# 6_eMMC.net
KiCad netlist of a schematic drawn in Altium Designer
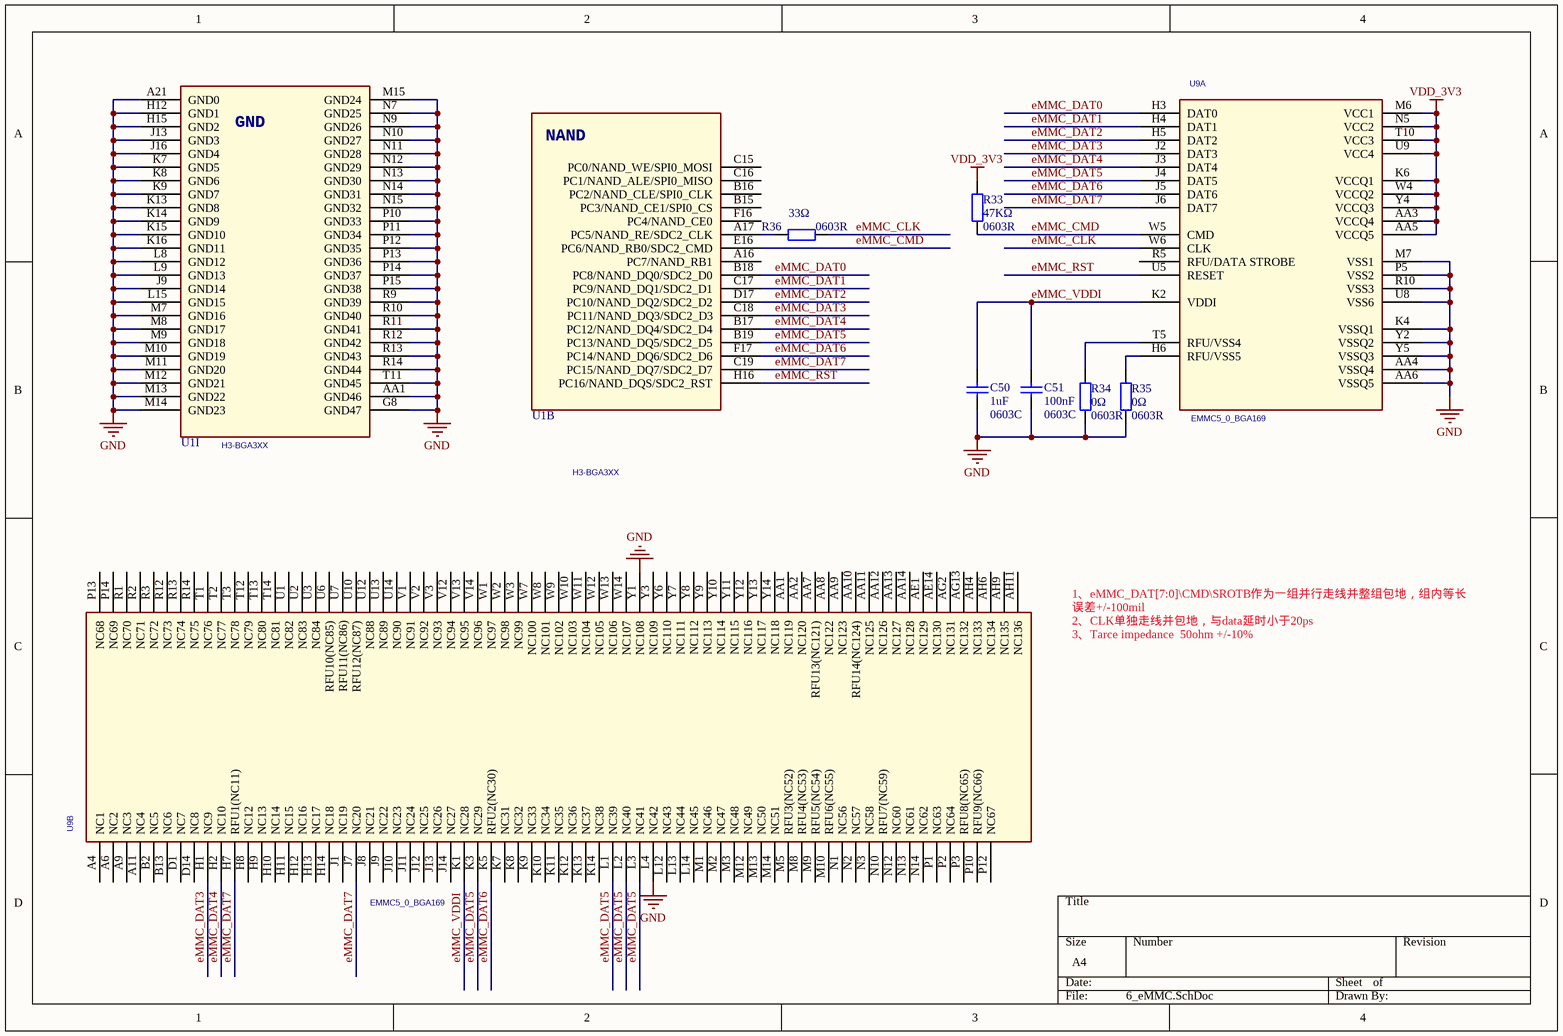
[diagram p0: 6_eMMC.SchDoc]

(export (version "E")
  (design (tool "Eeschema 10.0.6"))
  (components
    (comp (ref "C50")
      (value "1uF")
      (footprint "0603_C")
      (description "贴片电容")
      (fields (field (name "PACKAGE") "0603C"))
      (libsource (lib "Miscellaneous Devices LC") (part "0402 1nF (102) 10% 50V"))
    )
    (comp (ref "C51")
      (value "100nF")
      (footprint "0603_C")
      (description "贴片电容")
      (fields (field (name "PACKAGE") "0603C"))
      (libsource (lib "Miscellaneous Devices LC") (part "0402 1nF (102) 10% 50V"))
    )
    (comp (ref "R33")
      (value "47KΩ")
      (footprint "0603_R")
      (description "贴片电阻")
      (fields (field (name "PACKAGE") "0603R"))
      (libsource (lib "") (part "0402 1KΩ (1001) 1%_1"))
    )
    (comp (ref "R34")
      (value "0Ω")
      (footprint "0603_R")
      (description "贴片电阻")
      (fields (field (name "PACKAGE") "0603R"))
      (libsource (lib "") (part "0402 1KΩ (1001) 1%_1"))
    )
    (comp (ref "R35")
      (value "0Ω")
      (footprint "0603_R")
      (description "贴片电阻")
      (fields (field (name "PACKAGE") "0603R"))
      (libsource (lib "") (part "0402 1KΩ (1001) 1%_1"))
    )
    (comp (ref "R36")
      (value "33Ω")
      (footprint "0603_R")
      (description "贴片电阻")
      (fields (field (name "PACKAGE") "0603R"))
      (libsource (lib "Miscellaneous Devices LC") (part "0402 1KΩ (1001) 1%"))
    )
    (comp (ref "U1")
      (value "H3-BGA3XX")
      (footprint "BGA347P0_65B14X14")
      (libsource (lib "MAGNET_L") (part "H3-BGA3XX"))
    )
    (comp (ref "U9")
      (value "EMMC5_0_BGA169")
      (footprint "BGA169P0_50B12_00X16_00H1_00")
      (libsource (lib "H3_PROTOTYPE_DDR3_16X2_V3_0_20141113") (part "EMMC5_0_BGA169"))
    )
  )
  (nets
    (net (code "1") (name "/eMMC_CLK") (class "Default")
      (node (ref "R36") (pin "2") (pinfunction "2_2") (pintype "passive"))
      (node (ref "U9") (pin "W6") (pinfunction "CLK_W6") (pintype "passive"))
    )
    (net (code "2") (name "/eMMC_CMD") (class "Default")
      (node (ref "R33") (pin "2") (pinfunction "2_2") (pintype "passive"))
      (node (ref "U1") (pin "E16") (pinfunction "PC6/NAND_RB0/SDC2_CMD_E16") (pintype "passive"))
      (node (ref "U9") (pin "W5") (pinfunction "CMD_W5") (pintype "passive"))
    )
    (net (code "3") (name "/eMMC_DAT0") (class "Default")
      (node (ref "U1") (pin "B18") (pinfunction "PC8/NAND_DQ0/SDC2_D0_B18") (pintype "passive"))
      (node (ref "U9") (pin "H3") (pinfunction "DAT0_H3") (pintype "passive"))
    )
    (net (code "4") (name "/eMMC_DAT1") (class "Default")
      (node (ref "U1") (pin "C17") (pinfunction "PC9/NAND_DQ1/SDC2_D1_C17") (pintype "passive"))
      (node (ref "U9") (pin "H4") (pinfunction "DAT1_H4") (pintype "passive"))
    )
    (net (code "5") (name "/eMMC_DAT2") (class "Default")
      (node (ref "U1") (pin "D17") (pinfunction "PC10/NAND_DQ2/SDC2_D2_D17") (pintype "passive"))
      (node (ref "U9") (pin "H5") (pinfunction "DAT2_H5") (pintype "passive"))
    )
    (net (code "6") (name "/eMMC_DAT3") (class "Default")
      (node (ref "U1") (pin "C18") (pinfunction "PC11/NAND_DQ3/SDC2_D3_C18") (pintype "passive"))
      (node (ref "U9") (pin "H1") (pinfunction "NC9_H1") (pintype "passive"))
      (node (ref "U9") (pin "J2") (pinfunction "DAT3_J2") (pintype "passive"))
    )
    (net (code "7") (name "/eMMC_DAT4") (class "Default")
      (node (ref "U1") (pin "B17") (pinfunction "PC12/NAND_DQ4/SDC2_D4_B17") (pintype "passive"))
      (node (ref "U9") (pin "H2") (pinfunction "NC10_H2") (pintype "passive"))
      (node (ref "U9") (pin "J3") (pinfunction "DAT4_J3") (pintype "passive"))
    )
    (net (code "8") (name "/eMMC_DAT5") (class "Default")
      (node (ref "U1") (pin "B19") (pinfunction "PC13/NAND_DQ5/SDC2_D5_B19") (pintype "passive"))
      (node (ref "U9") (pin "J4") (pinfunction "DAT5_J4") (pintype "passive"))
      (node (ref "U9") (pin "K3") (pinfunction "NC29_K3") (pintype "passive"))
      (node (ref "U9") (pin "L1") (pinfunction "NC39_L1") (pintype "passive"))
      (node (ref "U9") (pin "L2") (pinfunction "NC40_L2") (pintype "passive"))
      (node (ref "U9") (pin "L3") (pinfunction "NC41_L3") (pintype "passive"))
    )
    (net (code "9") (name "/eMMC_DAT6") (class "Default")
      (node (ref "U1") (pin "F17") (pinfunction "PC14/NAND_DQ6/SDC2_D6_F17") (pintype "passive"))
      (node (ref "U9") (pin "J5") (pinfunction "DAT6_J5") (pintype "passive"))
      (node (ref "U9") (pin "K5") (pinfunction "RFU2(NC30)_K5") (pintype "passive"))
    )
    (net (code "10") (name "/eMMC_DAT7") (class "Default")
      (node (ref "U1") (pin "C19") (pinfunction "PC15/NAND_DQ7/SDC2_D7_C19") (pintype "passive"))
      (node (ref "U9") (pin "H7") (pinfunction "RFU1(NC11)_H7") (pintype "passive"))
      (node (ref "U9") (pin "J6") (pinfunction "DAT7_J6") (pintype "passive"))
      (node (ref "U9") (pin "J7") (pinfunction "NC20_J7") (pintype "passive"))
    )
    (net (code "11") (name "/eMMC_RST") (class "Default")
      (node (ref "U1") (pin "H16") (pinfunction "PC16/NAND_DQS/SDC2_RST_H16") (pintype "passive"))
      (node (ref "U9") (pin "U5") (pinfunction "RESET_U5") (pintype "passive"))
    )
    (net (code "12") (name "/eMMC_VDDI") (class "Default")
      (node (ref "C50") (pin "1") (pinfunction "1_1") (pintype "passive"))
      (node (ref "C51") (pin "1") (pinfunction "1_1") (pintype "passive"))
      (node (ref "U9") (pin "K1") (pinfunction "NC28_K1") (pintype "passive"))
      (node (ref "U9") (pin "K2") (pinfunction "VDDI_K2") (pintype "passive"))
    )
    (net (code "13") (name "GND") (class "Default")
      (node (ref "C50") (pin "2") (pinfunction "2_2") (pintype "passive"))
      (node (ref "C51") (pin "2") (pinfunction "2_2") (pintype "passive"))
      (node (ref "R34") (pin "2") (pinfunction "2_2") (pintype "passive"))
      (node (ref "R35") (pin "2") (pinfunction "2_2") (pintype "passive"))
      (node (ref "U1") (pin "A21") (pinfunction "GND0_A21") (pintype "passive"))
      (node (ref "U1") (pin "AA1") (pinfunction "GND46_AA1") (pintype "passive"))
      (node (ref "U1") (pin "G8") (pinfunction "GND47_G8") (pintype "passive"))
      (node (ref "U1") (pin "H12") (pinfunction "GND1_H12") (pintype "passive"))
      (node (ref "U1") (pin "H15") (pinfunction "GND2_H15") (pintype "passive"))
      (node (ref "U1") (pin "J13") (pinfunction "GND3_J13") (pintype "passive"))
      (node (ref "U1") (pin "J16") (pinfunction "GND4_J16") (pintype "passive"))
      (node (ref "U1") (pin "J9") (pinfunction "GND14_J9") (pintype "passive"))
      (node (ref "U1") (pin "K13") (pinfunction "GND8_K13") (pintype "passive"))
      (node (ref "U1") (pin "K14") (pinfunction "GND9_K14") (pintype "passive"))
      (node (ref "U1") (pin "K15") (pinfunction "GND10_K15") (pintype "passive"))
      (node (ref "U1") (pin "K16") (pinfunction "GND11_K16") (pintype "passive"))
      (node (ref "U1") (pin "K7") (pinfunction "GND5_K7") (pintype "passive"))
      (node (ref "U1") (pin "K8") (pinfunction "GND6_K8") (pintype "passive"))
      (node (ref "U1") (pin "K9") (pinfunction "GND7_K9") (pintype "passive"))
      (node (ref "U1") (pin "L15") (pinfunction "GND15_L15") (pintype "passive"))
      (node (ref "U1") (pin "L8") (pinfunction "GND12_L8") (pintype "passive"))
      (node (ref "U1") (pin "L9") (pinfunction "GND13_L9") (pintype "passive"))
      (node (ref "U1") (pin "M10") (pinfunction "GND19_M10") (pintype "passive"))
      (node (ref "U1") (pin "M11") (pinfunction "GND20_M11") (pintype "passive"))
      (node (ref "U1") (pin "M12") (pinfunction "GND21_M12") (pintype "passive"))
      (node (ref "U1") (pin "M13") (pinfunction "GND22_M13") (pintype "passive"))
      (node (ref "U1") (pin "M14") (pinfunction "GND23_M14") (pintype "passive"))
      (node (ref "U1") (pin "M15") (pinfunction "GND24_M15") (pintype "passive"))
      (node (ref "U1") (pin "M7") (pinfunction "GND16_M7") (pintype "passive"))
      (node (ref "U1") (pin "M8") (pinfunction "GND17_M8") (pintype "passive"))
      (node (ref "U1") (pin "M9") (pinfunction "GND18_M9") (pintype "passive"))
      (node (ref "U1") (pin "N10") (pinfunction "GND27_N10") (pintype "passive"))
      (node (ref "U1") (pin "N11") (pinfunction "GND28_N11") (pintype "passive"))
      (node (ref "U1") (pin "N12") (pinfunction "GND29_N12") (pintype "passive"))
      (node (ref "U1") (pin "N13") (pinfunction "GND30_N13") (pintype "passive"))
      (node (ref "U1") (pin "N14") (pinfunction "GND31_N14") (pintype "passive"))
      (node (ref "U1") (pin "N15") (pinfunction "GND32_N15") (pintype "passive"))
      (node (ref "U1") (pin "N7") (pinfunction "GND25_N7") (pintype "passive"))
      (node (ref "U1") (pin "N9") (pinfunction "GND26_N9") (pintype "passive"))
      (node (ref "U1") (pin "P10") (pinfunction "GND33_P10") (pintype "passive"))
      (node (ref "U1") (pin "P11") (pinfunction "GND34_P11") (pintype "passive"))
      (node (ref "U1") (pin "P12") (pinfunction "GND35_P12") (pintype "passive"))
      (node (ref "U1") (pin "P13") (pinfunction "GND36_P13") (pintype "passive"))
      (node (ref "U1") (pin "P14") (pinfunction "GND37_P14") (pintype "passive"))
      (node (ref "U1") (pin "P15") (pinfunction "GND38_P15") (pintype "passive"))
      (node (ref "U1") (pin "R10") (pinfunction "GND40_R10") (pintype "passive"))
      (node (ref "U1") (pin "R11") (pinfunction "GND41_R11") (pintype "passive"))
      (node (ref "U1") (pin "R12") (pinfunction "GND42_R12") (pintype "passive"))
      (node (ref "U1") (pin "R13") (pinfunction "GND43_R13") (pintype "passive"))
      (node (ref "U1") (pin "R14") (pinfunction "GND44_R14") (pintype "passive"))
      (node (ref "U1") (pin "R9") (pinfunction "GND39_R9") (pintype "passive"))
      (node (ref "U1") (pin "T11") (pinfunction "GND45_T11") (pintype "passive"))
      (node (ref "U9") (pin "AA4") (pinfunction "VSSQ4_AA4") (pintype "passive"))
      (node (ref "U9") (pin "AA6") (pinfunction "VSSQ5_AA6") (pintype "passive"))
      (node (ref "U9") (pin "K4") (pinfunction "VSSQ1_K4") (pintype "passive"))
      (node (ref "U9") (pin "L4") (pinfunction "NC42_L4") (pintype "passive"))
      (node (ref "U9") (pin "M7") (pinfunction "VSS1_M7") (pintype "passive"))
      (node (ref "U9") (pin "P5") (pinfunction "VSS2_P5") (pintype "passive"))
      (node (ref "U9") (pin "R10") (pinfunction "VSS3_R10") (pintype "passive"))
      (node (ref "U9") (pin "U8") (pinfunction "VSS6_U8") (pintype "passive"))
      (node (ref "U9") (pin "Y1") (pinfunction "NC108_Y1") (pintype "passive"))
      (node (ref "U9") (pin "Y2") (pinfunction "VSSQ2_Y2") (pintype "passive"))
      (node (ref "U9") (pin "Y5") (pinfunction "VSSQ3_Y5") (pintype "passive"))
    )
    (net (code "14") (name "Net-(U1B-PC5{slash}NAND_RE{slash}SDC2_CLK)") (class "Default")
      (node (ref "R36") (pin "1") (pinfunction "1_1") (pintype "passive"))
      (node (ref "U1") (pin "A17") (pinfunction "PC5/NAND_RE/SDC2_CLK_A17") (pintype "passive"))
    )
    (net (code "15") (name "Net-(U9A-RFU{slash}VSS4)") (class "Default")
      (node (ref "R34") (pin "1") (pinfunction "1_1") (pintype "passive"))
      (node (ref "U9") (pin "T5") (pinfunction "RFU/VSS4_T5") (pintype "passive"))
    )
    (net (code "16") (name "Net-(U9A-RFU{slash}VSS5)") (class "Default")
      (node (ref "R35") (pin "1") (pinfunction "1_1") (pintype "passive"))
      (node (ref "U9") (pin "H6") (pinfunction "RFU/VSS5_H6") (pintype "passive"))
    )
    (net (code "17") (name "VDD_3V3") (class "Default")
      (node (ref "R33") (pin "1") (pinfunction "1_1") (pintype "passive"))
      (node (ref "U9") (pin "AA3") (pinfunction "VCCQ4_AA3") (pintype "passive"))
      (node (ref "U9") (pin "AA5") (pinfunction "VCCQ5_AA5") (pintype "passive"))
      (node (ref "U9") (pin "K6") (pinfunction "VCCQ1_K6") (pintype "passive"))
      (node (ref "U9") (pin "M6") (pinfunction "VCC1_M6") (pintype "passive"))
      (node (ref "U9") (pin "N5") (pinfunction "VCC2_N5") (pintype "passive"))
      (node (ref "U9") (pin "T10") (pinfunction "VCC3_T10") (pintype "passive"))
      (node (ref "U9") (pin "U9") (pinfunction "VCC4_U9") (pintype "passive"))
      (node (ref "U9") (pin "W4") (pinfunction "VCCQ2_W4") (pintype "passive"))
      (node (ref "U9") (pin "Y4") (pinfunction "VCCQ3_Y4") (pintype "passive"))
    )
    (net (code "18") (name "unconnected-(U1B-PC0{slash}NAND_WE{slash}SPI0_MOSI-PadC15)") (class "Default")
      (node (ref "U1") (pin "C15") (pinfunction "PC0/NAND_WE/SPI0_MOSI_C15") (pintype "passive"))
    )
    (net (code "19") (name "unconnected-(U1B-PC1{slash}NAND_ALE{slash}SPI0_MISO-PadC16)") (class "Default")
      (node (ref "U1") (pin "C16") (pinfunction "PC1/NAND_ALE/SPI0_MISO_C16") (pintype "passive"))
    )
    (net (code "20") (name "unconnected-(U1B-PC2{slash}NAND_CLE{slash}SPI0_CLK-PadB16)") (class "Default")
      (node (ref "U1") (pin "B16") (pinfunction "PC2/NAND_CLE/SPI0_CLK_B16") (pintype "passive"))
    )
    (net (code "21") (name "unconnected-(U1B-PC3{slash}NAND_CE1{slash}SPI0_CS-PadB15)") (class "Default")
      (node (ref "U1") (pin "B15") (pinfunction "PC3/NAND_CE1/SPI0_CS_B15") (pintype "passive"))
    )
    (net (code "22") (name "unconnected-(U1B-PC4{slash}NAND_CE0-PadF16)") (class "Default")
      (node (ref "U1") (pin "F16") (pinfunction "PC4/NAND_CE0_F16") (pintype "passive"))
    )
    (net (code "23") (name "unconnected-(U1B-PC7{slash}NAND_RB1-PadA16)") (class "Default")
      (node (ref "U1") (pin "A16") (pinfunction "PC7/NAND_RB1_A16") (pintype "passive"))
    )
    (net (code "24") (name "unconnected-(U9A-RFU{slash}DATA_STROBE-PadR5)") (class "Default")
      (node (ref "U9") (pin "R5") (pinfunction "RFU/DATA_STROBE_R5") (pintype "passive"))
    )
    (net (code "25") (name "unconnected-(U9B-NC1-PadA4)") (class "Default")
      (node (ref "U9") (pin "A4") (pinfunction "NC1_A4") (pintype "passive"))
    )
    (net (code "26") (name "unconnected-(U9B-NC2-PadA6)") (class "Default")
      (node (ref "U9") (pin "A6") (pinfunction "NC2_A6") (pintype "passive"))
    )
    (net (code "27") (name "unconnected-(U9B-NC3-PadA9)") (class "Default")
      (node (ref "U9") (pin "A9") (pinfunction "NC3_A9") (pintype "passive"))
    )
    (net (code "28") (name "unconnected-(U9B-NC4-PadA11)") (class "Default")
      (node (ref "U9") (pin "A11") (pinfunction "NC4_A11") (pintype "passive"))
    )
    (net (code "29") (name "unconnected-(U9B-NC5-PadB2)") (class "Default")
      (node (ref "U9") (pin "B2") (pinfunction "NC5_B2") (pintype "passive"))
    )
    (net (code "30") (name "unconnected-(U9B-NC6-PadB13)") (class "Default")
      (node (ref "U9") (pin "B13") (pinfunction "NC6_B13") (pintype "passive"))
    )
    (net (code "31") (name "unconnected-(U9B-NC7-PadD1)") (class "Default")
      (node (ref "U9") (pin "D1") (pinfunction "NC7_D1") (pintype "passive"))
    )
    (net (code "32") (name "unconnected-(U9B-NC8-PadD14)") (class "Default")
      (node (ref "U9") (pin "D14") (pinfunction "NC8_D14") (pintype "passive"))
    )
    (net (code "33") (name "unconnected-(U9B-NC12-PadH8)") (class "Default")
      (node (ref "U9") (pin "H8") (pinfunction "NC12_H8") (pintype "passive"))
    )
    (net (code "34") (name "unconnected-(U9B-NC13-PadH9)") (class "Default")
      (node (ref "U9") (pin "H9") (pinfunction "NC13_H9") (pintype "passive"))
    )
    (net (code "35") (name "unconnected-(U9B-NC14-PadH10)") (class "Default")
      (node (ref "U9") (pin "H10") (pinfunction "NC14_H10") (pintype "passive"))
    )
    (net (code "36") (name "unconnected-(U9B-NC15-PadH11)") (class "Default")
      (node (ref "U9") (pin "H11") (pinfunction "NC15_H11") (pintype "passive"))
    )
    (net (code "37") (name "unconnected-(U9B-NC16-PadH12)") (class "Default")
      (node (ref "U9") (pin "H12") (pinfunction "NC16_H12") (pintype "passive"))
    )
    (net (code "38") (name "unconnected-(U9B-NC17-PadH13)") (class "Default")
      (node (ref "U9") (pin "H13") (pinfunction "NC17_H13") (pintype "passive"))
    )
    (net (code "39") (name "unconnected-(U9B-NC18-PadH14)") (class "Default")
      (node (ref "U9") (pin "H14") (pinfunction "NC18_H14") (pintype "passive"))
    )
    (net (code "40") (name "unconnected-(U9B-NC19-PadJ1)") (class "Default")
      (node (ref "U9") (pin "J1") (pinfunction "NC19_J1") (pintype "passive"))
    )
    (net (code "41") (name "unconnected-(U9B-NC21-PadJ8)") (class "Default")
      (node (ref "U9") (pin "J8") (pinfunction "NC21_J8") (pintype "passive"))
    )
    (net (code "42") (name "unconnected-(U9B-NC22-PadJ9)") (class "Default")
      (node (ref "U9") (pin "J9") (pinfunction "NC22_J9") (pintype "passive"))
    )
    (net (code "43") (name "unconnected-(U9B-NC23-PadJ10)") (class "Default")
      (node (ref "U9") (pin "J10") (pinfunction "NC23_J10") (pintype "passive"))
    )
    (net (code "44") (name "unconnected-(U9B-NC24-PadJ11)") (class "Default")
      (node (ref "U9") (pin "J11") (pinfunction "NC24_J11") (pintype "passive"))
    )
    (net (code "45") (name "unconnected-(U9B-NC25-PadJ12)") (class "Default")
      (node (ref "U9") (pin "J12") (pinfunction "NC25_J12") (pintype "passive"))
    )
    (net (code "46") (name "unconnected-(U9B-NC26-PadJ13)") (class "Default")
      (node (ref "U9") (pin "J13") (pinfunction "NC26_J13") (pintype "passive"))
    )
    (net (code "47") (name "unconnected-(U9B-NC27-PadJ14)") (class "Default")
      (node (ref "U9") (pin "J14") (pinfunction "NC27_J14") (pintype "passive"))
    )
    (net (code "48") (name "unconnected-(U9B-NC31-PadK7)") (class "Default")
      (node (ref "U9") (pin "K7") (pinfunction "NC31_K7") (pintype "passive"))
    )
    (net (code "49") (name "unconnected-(U9B-NC32-PadK8)") (class "Default")
      (node (ref "U9") (pin "K8") (pinfunction "NC32_K8") (pintype "passive"))
    )
    (net (code "50") (name "unconnected-(U9B-NC33-PadK9)") (class "Default")
      (node (ref "U9") (pin "K9") (pinfunction "NC33_K9") (pintype "passive"))
    )
    (net (code "51") (name "unconnected-(U9B-NC34-PadK10)") (class "Default")
      (node (ref "U9") (pin "K10") (pinfunction "NC34_K10") (pintype "passive"))
    )
    (net (code "52") (name "unconnected-(U9B-NC35-PadK11)") (class "Default")
      (node (ref "U9") (pin "K11") (pinfunction "NC35_K11") (pintype "passive"))
    )
    (net (code "53") (name "unconnected-(U9B-NC36-PadK12)") (class "Default")
      (node (ref "U9") (pin "K12") (pinfunction "NC36_K12") (pintype "passive"))
    )
    (net (code "54") (name "unconnected-(U9B-NC37-PadK13)") (class "Default")
      (node (ref "U9") (pin "K13") (pinfunction "NC37_K13") (pintype "passive"))
    )
    (net (code "55") (name "unconnected-(U9B-NC38-PadK14)") (class "Default")
      (node (ref "U9") (pin "K14") (pinfunction "NC38_K14") (pintype "passive"))
    )
    (net (code "56") (name "unconnected-(U9B-NC43-PadL12)") (class "Default")
      (node (ref "U9") (pin "L12") (pinfunction "NC43_L12") (pintype "passive"))
    )
    (net (code "57") (name "unconnected-(U9B-NC44-PadL13)") (class "Default")
      (node (ref "U9") (pin "L13") (pinfunction "NC44_L13") (pintype "passive"))
    )
    (net (code "58") (name "unconnected-(U9B-NC45-PadL14)") (class "Default")
      (node (ref "U9") (pin "L14") (pinfunction "NC45_L14") (pintype "passive"))
    )
    (net (code "59") (name "unconnected-(U9B-NC46-PadM1)") (class "Default")
      (node (ref "U9") (pin "M1") (pinfunction "NC46_M1") (pintype "passive"))
    )
    (net (code "60") (name "unconnected-(U9B-NC47-PadM2)") (class "Default")
      (node (ref "U9") (pin "M2") (pinfunction "NC47_M2") (pintype "passive"))
    )
    (net (code "61") (name "unconnected-(U9B-NC48-PadM3)") (class "Default")
      (node (ref "U9") (pin "M3") (pinfunction "NC48_M3") (pintype "passive"))
    )
    (net (code "62") (name "unconnected-(U9B-NC49-PadM12)") (class "Default")
      (node (ref "U9") (pin "M12") (pinfunction "NC49_M12") (pintype "passive"))
    )
    (net (code "63") (name "unconnected-(U9B-NC50-PadM13)") (class "Default")
      (node (ref "U9") (pin "M13") (pinfunction "NC50_M13") (pintype "passive"))
    )
    (net (code "64") (name "unconnected-(U9B-NC51-PadM14)") (class "Default")
      (node (ref "U9") (pin "M14") (pinfunction "NC51_M14") (pintype "passive"))
    )
    (net (code "65") (name "unconnected-(U9B-NC56-PadN1)") (class "Default")
      (node (ref "U9") (pin "N1") (pinfunction "NC56_N1") (pintype "passive"))
    )
    (net (code "66") (name "unconnected-(U9B-NC57-PadN2)") (class "Default")
      (node (ref "U9") (pin "N2") (pinfunction "NC57_N2") (pintype "passive"))
    )
    (net (code "67") (name "unconnected-(U9B-NC58-PadN3)") (class "Default")
      (node (ref "U9") (pin "N3") (pinfunction "NC58_N3") (pintype "passive"))
    )
    (net (code "68") (name "unconnected-(U9B-NC60-PadN12)") (class "Default")
      (node (ref "U9") (pin "N12") (pinfunction "NC60_N12") (pintype "passive"))
    )
    (net (code "69") (name "unconnected-(U9B-NC61-PadN13)") (class "Default")
      (node (ref "U9") (pin "N13") (pinfunction "NC61_N13") (pintype "passive"))
    )
    (net (code "70") (name "unconnected-(U9B-NC62-PadN14)") (class "Default")
      (node (ref "U9") (pin "N14") (pinfunction "NC62_N14") (pintype "passive"))
    )
    (net (code "71") (name "unconnected-(U9B-NC63-PadP1)") (class "Default")
      (node (ref "U9") (pin "P1") (pinfunction "NC63_P1") (pintype "passive"))
    )
    (net (code "72") (name "unconnected-(U9B-NC64-PadP2)") (class "Default")
      (node (ref "U9") (pin "P2") (pinfunction "NC64_P2") (pintype "passive"))
    )
    (net (code "73") (name "unconnected-(U9B-NC67-PadP12)") (class "Default")
      (node (ref "U9") (pin "P12") (pinfunction "NC67_P12") (pintype "passive"))
    )
    (net (code "74") (name "unconnected-(U9B-NC68-PadP13)") (class "Default")
      (node (ref "U9") (pin "P13") (pinfunction "NC68_P13") (pintype "passive"))
    )
    (net (code "75") (name "unconnected-(U9B-NC69-PadP14)") (class "Default")
      (node (ref "U9") (pin "P14") (pinfunction "NC69_P14") (pintype "passive"))
    )
    (net (code "76") (name "unconnected-(U9B-NC70-PadR1)") (class "Default")
      (node (ref "U9") (pin "R1") (pinfunction "NC70_R1") (pintype "passive"))
    )
    (net (code "77") (name "unconnected-(U9B-NC71-PadR2)") (class "Default")
      (node (ref "U9") (pin "R2") (pinfunction "NC71_R2") (pintype "passive"))
    )
    (net (code "78") (name "unconnected-(U9B-NC72-PadR3)") (class "Default")
      (node (ref "U9") (pin "R3") (pinfunction "NC72_R3") (pintype "passive"))
    )
    (net (code "79") (name "unconnected-(U9B-NC73-PadR12)") (class "Default")
      (node (ref "U9") (pin "R12") (pinfunction "NC73_R12") (pintype "passive"))
    )
    (net (code "80") (name "unconnected-(U9B-NC74-PadR13)") (class "Default")
      (node (ref "U9") (pin "R13") (pinfunction "NC74_R13") (pintype "passive"))
    )
    (net (code "81") (name "unconnected-(U9B-NC75-PadR14)") (class "Default")
      (node (ref "U9") (pin "R14") (pinfunction "NC75_R14") (pintype "passive"))
    )
    (net (code "82") (name "unconnected-(U9B-NC76-PadT1)") (class "Default")
      (node (ref "U9") (pin "T1") (pinfunction "NC76_T1") (pintype "passive"))
    )
    (net (code "83") (name "unconnected-(U9B-NC77-PadT2)") (class "Default")
      (node (ref "U9") (pin "T2") (pinfunction "NC77_T2") (pintype "passive"))
    )
    (net (code "84") (name "unconnected-(U9B-NC78-PadT3)") (class "Default")
      (node (ref "U9") (pin "T3") (pinfunction "NC78_T3") (pintype "passive"))
    )
    (net (code "85") (name "unconnected-(U9B-NC79-PadT12)") (class "Default")
      (node (ref "U9") (pin "T12") (pinfunction "NC79_T12") (pintype "passive"))
    )
    (net (code "86") (name "unconnected-(U9B-NC80-PadT13)") (class "Default")
      (node (ref "U9") (pin "T13") (pinfunction "NC80_T13") (pintype "passive"))
    )
    (net (code "87") (name "unconnected-(U9B-NC81-PadT14)") (class "Default")
      (node (ref "U9") (pin "T14") (pinfunction "NC81_T14") (pintype "passive"))
    )
    (net (code "88") (name "unconnected-(U9B-NC82-PadU1)") (class "Default")
      (node (ref "U9") (pin "U1") (pinfunction "NC82_U1") (pintype "passive"))
    )
    (net (code "89") (name "unconnected-(U9B-NC83-PadU2)") (class "Default")
      (node (ref "U9") (pin "U2") (pinfunction "NC83_U2") (pintype "passive"))
    )
    (net (code "90") (name "unconnected-(U9B-NC84-PadU3)") (class "Default")
      (node (ref "U9") (pin "U3") (pinfunction "NC84_U3") (pintype "passive"))
    )
    (net (code "91") (name "unconnected-(U9B-NC88-PadU12)") (class "Default")
      (node (ref "U9") (pin "U12") (pinfunction "NC88_U12") (pintype "passive"))
    )
    (net (code "92") (name "unconnected-(U9B-NC89-PadU13)") (class "Default")
      (node (ref "U9") (pin "U13") (pinfunction "NC89_U13") (pintype "passive"))
    )
    (net (code "93") (name "unconnected-(U9B-NC90-PadU14)") (class "Default")
      (node (ref "U9") (pin "U14") (pinfunction "NC90_U14") (pintype "passive"))
    )
    (net (code "94") (name "unconnected-(U9B-NC91-PadV1)") (class "Default")
      (node (ref "U9") (pin "V1") (pinfunction "NC91_V1") (pintype "passive"))
    )
    (net (code "95") (name "unconnected-(U9B-NC92-PadV2)") (class "Default")
      (node (ref "U9") (pin "V2") (pinfunction "NC92_V2") (pintype "passive"))
    )
    (net (code "96") (name "unconnected-(U9B-NC93-PadV3)") (class "Default")
      (node (ref "U9") (pin "V3") (pinfunction "NC93_V3") (pintype "passive"))
    )
    (net (code "97") (name "unconnected-(U9B-NC94-PadV12)") (class "Default")
      (node (ref "U9") (pin "V12") (pinfunction "NC94_V12") (pintype "passive"))
    )
    (net (code "98") (name "unconnected-(U9B-NC95-PadV13)") (class "Default")
      (node (ref "U9") (pin "V13") (pinfunction "NC95_V13") (pintype "passive"))
    )
    (net (code "99") (name "unconnected-(U9B-NC96-PadV14)") (class "Default")
      (node (ref "U9") (pin "V14") (pinfunction "NC96_V14") (pintype "passive"))
    )
    (net (code "100") (name "unconnected-(U9B-NC97-PadW1)") (class "Default")
      (node (ref "U9") (pin "W1") (pinfunction "NC97_W1") (pintype "passive"))
    )
    (net (code "101") (name "unconnected-(U9B-NC98-PadW2)") (class "Default")
      (node (ref "U9") (pin "W2") (pinfunction "NC98_W2") (pintype "passive"))
    )
    (net (code "102") (name "unconnected-(U9B-NC99-PadW3)") (class "Default")
      (node (ref "U9") (pin "W3") (pinfunction "NC99_W3") (pintype "passive"))
    )
    (net (code "103") (name "unconnected-(U9B-NC100-PadW7)") (class "Default")
      (node (ref "U9") (pin "W7") (pinfunction "NC100_W7") (pintype "passive"))
    )
    (net (code "104") (name "unconnected-(U9B-NC101-PadW8)") (class "Default")
      (node (ref "U9") (pin "W8") (pinfunction "NC101_W8") (pintype "passive"))
    )
    (net (code "105") (name "unconnected-(U9B-NC102-PadW9)") (class "Default")
      (node (ref "U9") (pin "W9") (pinfunction "NC102_W9") (pintype "passive"))
    )
    (net (code "106") (name "unconnected-(U9B-NC103-PadW10)") (class "Default")
      (node (ref "U9") (pin "W10") (pinfunction "NC103_W10") (pintype "passive"))
    )
    (net (code "107") (name "unconnected-(U9B-NC104-PadW11)") (class "Default")
      (node (ref "U9") (pin "W11") (pinfunction "NC104_W11") (pintype "passive"))
    )
    (net (code "108") (name "unconnected-(U9B-NC105-PadW12)") (class "Default")
      (node (ref "U9") (pin "W12") (pinfunction "NC105_W12") (pintype "passive"))
    )
    (net (code "109") (name "unconnected-(U9B-NC106-PadW13)") (class "Default")
      (node (ref "U9") (pin "W13") (pinfunction "NC106_W13") (pintype "passive"))
    )
    (net (code "110") (name "unconnected-(U9B-NC107-PadW14)") (class "Default")
      (node (ref "U9") (pin "W14") (pinfunction "NC107_W14") (pintype "passive"))
    )
    (net (code "111") (name "unconnected-(U9B-NC109-PadY3)") (class "Default")
      (node (ref "U9") (pin "Y3") (pinfunction "NC109_Y3") (pintype "passive"))
    )
    (net (code "112") (name "unconnected-(U9B-NC110-PadY6)") (class "Default")
      (node (ref "U9") (pin "Y6") (pinfunction "NC110_Y6") (pintype "passive"))
    )
    (net (code "113") (name "unconnected-(U9B-NC111-PadY7)") (class "Default")
      (node (ref "U9") (pin "Y7") (pinfunction "NC111_Y7") (pintype "passive"))
    )
    (net (code "114") (name "unconnected-(U9B-NC112-PadY8)") (class "Default")
      (node (ref "U9") (pin "Y8") (pinfunction "NC112_Y8") (pintype "passive"))
    )
    (net (code "115") (name "unconnected-(U9B-NC113-PadY9)") (class "Default")
      (node (ref "U9") (pin "Y9") (pinfunction "NC113_Y9") (pintype "passive"))
    )
    (net (code "116") (name "unconnected-(U9B-NC114-PadY10)") (class "Default")
      (node (ref "U9") (pin "Y10") (pinfunction "NC114_Y10") (pintype "passive"))
    )
    (net (code "117") (name "unconnected-(U9B-NC115-PadY11)") (class "Default")
      (node (ref "U9") (pin "Y11") (pinfunction "NC115_Y11") (pintype "passive"))
    )
    (net (code "118") (name "unconnected-(U9B-NC116-PadY12)") (class "Default")
      (node (ref "U9") (pin "Y12") (pinfunction "NC116_Y12") (pintype "passive"))
    )
    (net (code "119") (name "unconnected-(U9B-NC117-PadY13)") (class "Default")
      (node (ref "U9") (pin "Y13") (pinfunction "NC117_Y13") (pintype "passive"))
    )
    (net (code "120") (name "unconnected-(U9B-NC118-PadY14)") (class "Default")
      (node (ref "U9") (pin "Y14") (pinfunction "NC118_Y14") (pintype "passive"))
    )
    (net (code "121") (name "unconnected-(U9B-NC119-PadAA1)") (class "Default")
      (node (ref "U9") (pin "AA1") (pinfunction "NC119_AA1") (pintype "passive"))
    )
    (net (code "122") (name "unconnected-(U9B-NC120-PadAA2)") (class "Default")
      (node (ref "U9") (pin "AA2") (pinfunction "NC120_AA2") (pintype "passive"))
    )
    (net (code "123") (name "unconnected-(U9B-NC122-PadAA8)") (class "Default")
      (node (ref "U9") (pin "AA8") (pinfunction "NC122_AA8") (pintype "passive"))
    )
    (net (code "124") (name "unconnected-(U9B-NC123-PadAA9)") (class "Default")
      (node (ref "U9") (pin "AA9") (pinfunction "NC123_AA9") (pintype "passive"))
    )
    (net (code "125") (name "unconnected-(U9B-NC125-PadAA11)") (class "Default")
      (node (ref "U9") (pin "AA11") (pinfunction "NC125_AA11") (pintype "passive"))
    )
    (net (code "126") (name "unconnected-(U9B-NC126-PadAA12)") (class "Default")
      (node (ref "U9") (pin "AA12") (pinfunction "NC126_AA12") (pintype "passive"))
    )
    (net (code "127") (name "unconnected-(U9B-NC127-PadAA13)") (class "Default")
      (node (ref "U9") (pin "AA13") (pinfunction "NC127_AA13") (pintype "passive"))
    )
    (net (code "128") (name "unconnected-(U9B-NC128-PadAA14)") (class "Default")
      (node (ref "U9") (pin "AA14") (pinfunction "NC128_AA14") (pintype "passive"))
    )
    (net (code "129") (name "unconnected-(U9B-NC129-PadAE1)") (class "Default")
      (node (ref "U9") (pin "AE1") (pinfunction "NC129_AE1") (pintype "passive"))
    )
    (net (code "130") (name "unconnected-(U9B-NC130-PadAE14)") (class "Default")
      (node (ref "U9") (pin "AE14") (pinfunction "NC130_AE14") (pintype "passive"))
    )
    (net (code "131") (name "unconnected-(U9B-NC131-PadAG2)") (class "Default")
      (node (ref "U9") (pin "AG2") (pinfunction "NC131_AG2") (pintype "passive"))
    )
    (net (code "132") (name "unconnected-(U9B-NC132-PadAG13)") (class "Default")
      (node (ref "U9") (pin "AG13") (pinfunction "NC132_AG13") (pintype "passive"))
    )
    (net (code "133") (name "unconnected-(U9B-NC133-PadAH4)") (class "Default")
      (node (ref "U9") (pin "AH4") (pinfunction "NC133_AH4") (pintype "passive"))
    )
    (net (code "134") (name "unconnected-(U9B-NC134-PadAH6)") (class "Default")
      (node (ref "U9") (pin "AH6") (pinfunction "NC134_AH6") (pintype "passive"))
    )
    (net (code "135") (name "unconnected-(U9B-NC135-PadAH9)") (class "Default")
      (node (ref "U9") (pin "AH9") (pinfunction "NC135_AH9") (pintype "passive"))
    )
    (net (code "136") (name "unconnected-(U9B-NC136-PadAH11)") (class "Default")
      (node (ref "U9") (pin "AH11") (pinfunction "NC136_AH11") (pintype "passive"))
    )
    (net (code "137") (name "unconnected-(U9B-RFU3(NC52)-PadM5)") (class "Default")
      (node (ref "U9") (pin "M5") (pinfunction "RFU3(NC52)_M5") (pintype "passive"))
    )
    (net (code "138") (name "unconnected-(U9B-RFU4(NC53)-PadM8)") (class "Default")
      (node (ref "U9") (pin "M8") (pinfunction "RFU4(NC53)_M8") (pintype "passive"))
    )
    (net (code "139") (name "unconnected-(U9B-RFU5(NC54)-PadM9)") (class "Default")
      (node (ref "U9") (pin "M9") (pinfunction "RFU5(NC54)_M9") (pintype "passive"))
    )
    (net (code "140") (name "unconnected-(U9B-RFU6(NC55)-PadM10)") (class "Default")
      (node (ref "U9") (pin "M10") (pinfunction "RFU6(NC55)_M10") (pintype "passive"))
    )
    (net (code "141") (name "unconnected-(U9B-RFU7(NC59)-PadN10)") (class "Default")
      (node (ref "U9") (pin "N10") (pinfunction "RFU7(NC59)_N10") (pintype "passive"))
    )
    (net (code "142") (name "unconnected-(U9B-RFU8(NC65)-PadP3)") (class "Default")
      (node (ref "U9") (pin "P3") (pinfunction "RFU8(NC65)_P3") (pintype "passive"))
    )
    (net (code "143") (name "unconnected-(U9B-RFU9(NC66)-PadP10)") (class "Default")
      (node (ref "U9") (pin "P10") (pinfunction "RFU9(NC66)_P10") (pintype "passive"))
    )
    (net (code "144") (name "unconnected-(U9B-RFU10(NC85)-PadU6)") (class "Default")
      (node (ref "U9") (pin "U6") (pinfunction "RFU10(NC85)_U6") (pintype "passive"))
    )
    (net (code "145") (name "unconnected-(U9B-RFU11(NC86)-PadU7)") (class "Default")
      (node (ref "U9") (pin "U7") (pinfunction "RFU11(NC86)_U7") (pintype "passive"))
    )
    (net (code "146") (name "unconnected-(U9B-RFU12(NC87)-PadU10)") (class "Default")
      (node (ref "U9") (pin "U10") (pinfunction "RFU12(NC87)_U10") (pintype "passive"))
    )
    (net (code "147") (name "unconnected-(U9B-RFU13(NC121)-PadAA7)") (class "Default")
      (node (ref "U9") (pin "AA7") (pinfunction "RFU13(NC121)_AA7") (pintype "passive"))
    )
    (net (code "148") (name "unconnected-(U9B-RFU14(NC124)-PadAA10)") (class "Default")
      (node (ref "U9") (pin "AA10") (pinfunction "RFU14(NC124)_AA10") (pintype "passive"))
    )
  )
)
